# midi2board.net
KiCad netlist of a schematic drawn in EAGLE
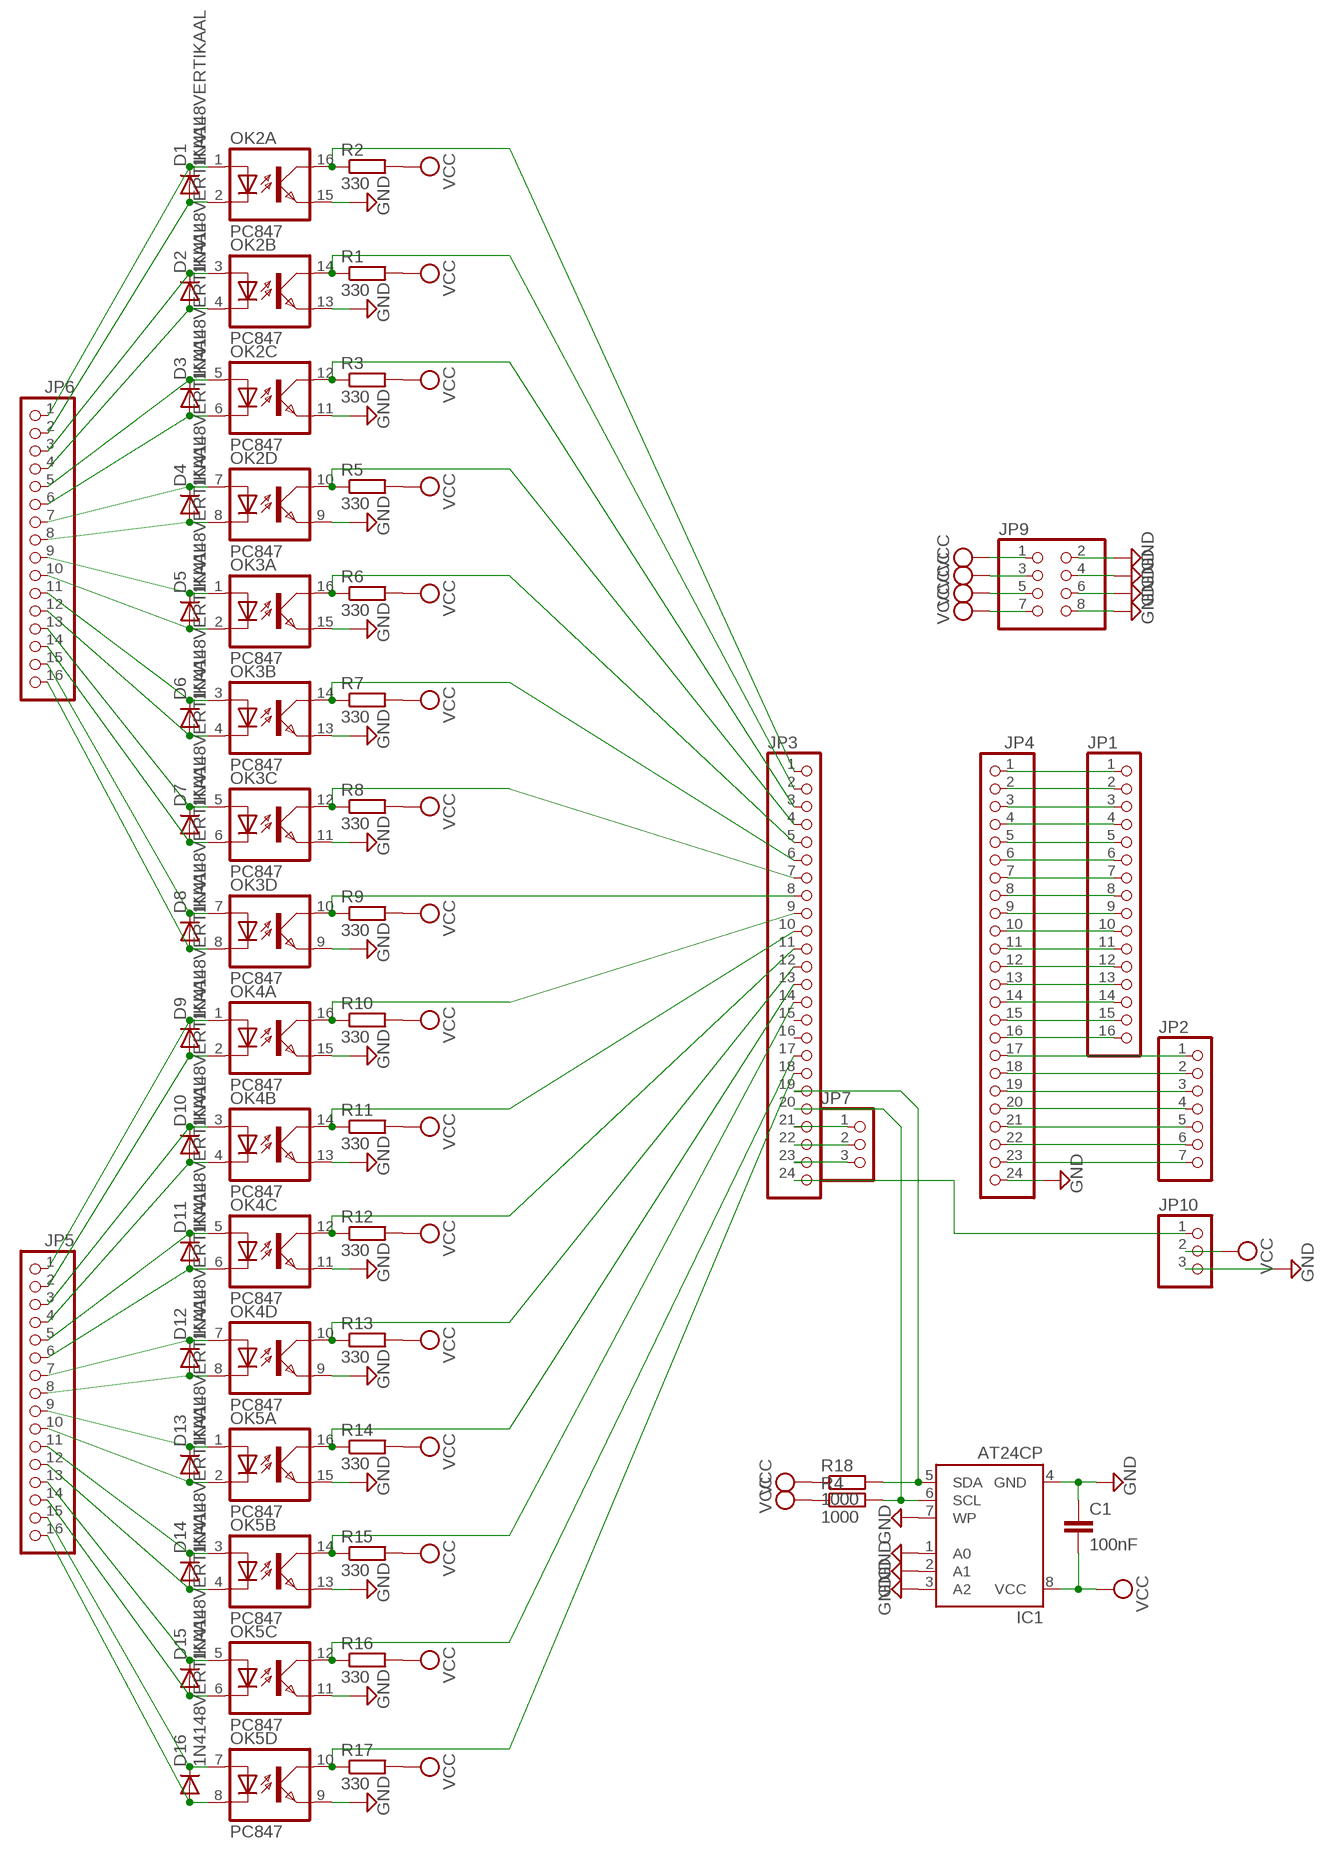
[diagram p0: schematic, sheet 1]

(export (version "E")
  (design (tool "Eeschema 10.0.6"))
  (components
    (comp (ref "C1")
      (value "100nF")
      (footprint "eagle-import:C5B2.5")
      (libsource (lib "eagle-import") (part "C5/2.5"))
    )
    (comp (ref "D1")
      (value "1N4148VERTIKAAL")
      (footprint "eagle-import:RAD2,5")
      (libsource (lib "eagle-import") (part "1N4148VERTIKAAL"))
    )
    (comp (ref "D2")
      (value "1N4148VERTIKAAL")
      (footprint "eagle-import:RAD2,5")
      (libsource (lib "eagle-import") (part "1N4148VERTIKAAL"))
    )
    (comp (ref "D3")
      (value "1N4148VERTIKAAL")
      (footprint "eagle-import:RAD2,5")
      (libsource (lib "eagle-import") (part "1N4148VERTIKAAL"))
    )
    (comp (ref "D4")
      (value "1N4148VERTIKAAL")
      (footprint "eagle-import:RAD2,5")
      (libsource (lib "eagle-import") (part "1N4148VERTIKAAL"))
    )
    (comp (ref "D5")
      (value "1N4148VERTIKAAL")
      (footprint "eagle-import:RAD2,5")
      (libsource (lib "eagle-import") (part "1N4148VERTIKAAL"))
    )
    (comp (ref "D6")
      (value "1N4148VERTIKAAL")
      (footprint "eagle-import:RAD2,5")
      (libsource (lib "eagle-import") (part "1N4148VERTIKAAL"))
    )
    (comp (ref "D7")
      (value "1N4148VERTIKAAL")
      (footprint "eagle-import:RAD2,5")
      (libsource (lib "eagle-import") (part "1N4148VERTIKAAL"))
    )
    (comp (ref "D8")
      (value "1N4148VERTIKAAL")
      (footprint "eagle-import:RAD2,5")
      (libsource (lib "eagle-import") (part "1N4148VERTIKAAL"))
    )
    (comp (ref "D9")
      (value "1N4148VERTIKAAL")
      (footprint "eagle-import:RAD2,5")
      (libsource (lib "eagle-import") (part "1N4148VERTIKAAL"))
    )
    (comp (ref "D10")
      (value "1N4148VERTIKAAL")
      (footprint "eagle-import:RAD2,5")
      (libsource (lib "eagle-import") (part "1N4148VERTIKAAL"))
    )
    (comp (ref "D11")
      (value "1N4148VERTIKAAL")
      (footprint "eagle-import:RAD2,5")
      (libsource (lib "eagle-import") (part "1N4148VERTIKAAL"))
    )
    (comp (ref "D12")
      (value "1N4148VERTIKAAL")
      (footprint "eagle-import:RAD2,5")
      (libsource (lib "eagle-import") (part "1N4148VERTIKAAL"))
    )
    (comp (ref "D13")
      (value "1N4148VERTIKAAL")
      (footprint "eagle-import:RAD2,5")
      (libsource (lib "eagle-import") (part "1N4148VERTIKAAL"))
    )
    (comp (ref "D14")
      (value "1N4148VERTIKAAL")
      (footprint "eagle-import:RAD2,5")
      (libsource (lib "eagle-import") (part "1N4148VERTIKAAL"))
    )
    (comp (ref "D15")
      (value "1N4148VERTIKAAL")
      (footprint "eagle-import:RAD2,5")
      (libsource (lib "eagle-import") (part "1N4148VERTIKAAL"))
    )
    (comp (ref "D16")
      (value "1N4148VERTIKAAL")
      (footprint "eagle-import:RAD2,5")
      (libsource (lib "eagle-import") (part "1N4148VERTIKAAL"))
    )
    (comp (ref "IC1")
      (value "AT24CP")
      (footprint "eagle-import:DIL08")
      (fields (field (name "MPN") "AT24C1024BW-SH-B"))
      (libsource (lib "eagle-import") (part "AT24CP"))
    )
    (comp (ref "JP1")
      (value "PINHD-1X16")
      (footprint "eagle-import:1X16")
      (libsource (lib "eagle-import") (part "PINHD-1X16"))
    )
    (comp (ref "JP2")
      (value "PINHD-1X7")
      (footprint "eagle-import:1X07")
      (libsource (lib "eagle-import") (part "PINHD-1X7"))
    )
    (comp (ref "JP3")
      (value "PINHD-1X24")
      (footprint "eagle-import:1X24")
      (libsource (lib "eagle-import") (part "PINHD-1X24"))
    )
    (comp (ref "JP4")
      (value "PINHD-1X24")
      (footprint "eagle-import:1X24")
      (libsource (lib "eagle-import") (part "PINHD-1X24"))
    )
    (comp (ref "JP5")
      (value "PINHD-1X16")
      (footprint "eagle-import:1X16")
      (libsource (lib "eagle-import") (part "PINHD-1X16"))
    )
    (comp (ref "JP6")
      (value "PINHD-1X16")
      (footprint "eagle-import:1X16")
      (libsource (lib "eagle-import") (part "PINHD-1X16"))
    )
    (comp (ref "JP7")
      (value "PINHD-1X3")
      (footprint "eagle-import:1X03")
      (libsource (lib "eagle-import") (part "PINHD-1X3"))
    )
    (comp (ref "JP9")
      (value "PINHD-2X4")
      (footprint "eagle-import:2X04")
      (libsource (lib "eagle-import") (part "PINHD-2X4"))
    )
    (comp (ref "JP10")
      (value "PINHD-1X3")
      (footprint "eagle-import:1X03")
      (libsource (lib "eagle-import") (part "PINHD-1X3"))
    )
    (comp (ref "OK2")
      (value "PC847")
      (footprint "eagle-import:DIL16")
      (libsource (lib "eagle-import") (part "PC847"))
    )
    (comp (ref "OK3")
      (value "PC847")
      (footprint "eagle-import:DIL16")
      (libsource (lib "eagle-import") (part "PC847"))
    )
    (comp (ref "OK4")
      (value "PC847")
      (footprint "eagle-import:DIL16")
      (libsource (lib "eagle-import") (part "PC847"))
    )
    (comp (ref "OK5")
      (value "PC847")
      (footprint "eagle-import:DIL16")
      (libsource (lib "eagle-import") (part "PC847"))
    )
    (comp (ref "R1")
      (value "330")
      (footprint "eagle-import:0207_10")
      (libsource (lib "eagle-import") (part "R-EU_0207/10"))
    )
    (comp (ref "R2")
      (value "330")
      (footprint "eagle-import:0207_10")
      (libsource (lib "eagle-import") (part "R-EU_0207/10"))
    )
    (comp (ref "R3")
      (value "330")
      (footprint "eagle-import:0207_10")
      (libsource (lib "eagle-import") (part "R-EU_0207/10"))
    )
    (comp (ref "R4")
      (value "1000")
      (footprint "eagle-import:0207_10")
      (libsource (lib "eagle-import") (part "R-EU_0207/10"))
    )
    (comp (ref "R5")
      (value "330")
      (footprint "eagle-import:0207_10")
      (libsource (lib "eagle-import") (part "R-EU_0207/10"))
    )
    (comp (ref "R6")
      (value "330")
      (footprint "eagle-import:0207_10")
      (libsource (lib "eagle-import") (part "R-EU_0207/10"))
    )
    (comp (ref "R7")
      (value "330")
      (footprint "eagle-import:0207_10")
      (libsource (lib "eagle-import") (part "R-EU_0207/10"))
    )
    (comp (ref "R8")
      (value "330")
      (footprint "eagle-import:0207_10")
      (libsource (lib "eagle-import") (part "R-EU_0207/10"))
    )
    (comp (ref "R9")
      (value "330")
      (footprint "eagle-import:0207_10")
      (libsource (lib "eagle-import") (part "R-EU_0207/10"))
    )
    (comp (ref "R10")
      (value "330")
      (footprint "eagle-import:0207_10")
      (libsource (lib "eagle-import") (part "R-EU_0207/10"))
    )
    (comp (ref "R11")
      (value "330")
      (footprint "eagle-import:0207_10")
      (libsource (lib "eagle-import") (part "R-EU_0207/10"))
    )
    (comp (ref "R12")
      (value "330")
      (footprint "eagle-import:0207_10")
      (libsource (lib "eagle-import") (part "R-EU_0207/10"))
    )
    (comp (ref "R13")
      (value "330")
      (footprint "eagle-import:0207_10")
      (libsource (lib "eagle-import") (part "R-EU_0207/10"))
    )
    (comp (ref "R14")
      (value "330")
      (footprint "eagle-import:0207_10")
      (libsource (lib "eagle-import") (part "R-EU_0207/10"))
    )
    (comp (ref "R15")
      (value "330")
      (footprint "eagle-import:0207_10")
      (libsource (lib "eagle-import") (part "R-EU_0207/10"))
    )
    (comp (ref "R16")
      (value "330")
      (footprint "eagle-import:0207_10")
      (libsource (lib "eagle-import") (part "R-EU_0207/10"))
    )
    (comp (ref "R17")
      (value "330")
      (footprint "eagle-import:0207_10")
      (libsource (lib "eagle-import") (part "R-EU_0207/10"))
    )
    (comp (ref "R18")
      (value "1000")
      (footprint "eagle-import:0207_10")
      (libsource (lib "eagle-import") (part "R-EU_0207/10"))
    )
  )
  (nets
    (net (code "1") (name "GND") (class "Default")
      (node (ref "C1") (pin "1") (pinfunction "1_1") (pintype "passive"))
      (node (ref "IC1") (pin "1") (pinfunction "A0_1") (pintype "input"))
      (node (ref "IC1") (pin "2") (pinfunction "A1_2") (pintype "input"))
      (node (ref "IC1") (pin "3") (pinfunction "A2_3") (pintype "input"))
      (node (ref "IC1") (pin "4") (pinfunction "GND_4") (pintype "power_in"))
      (node (ref "IC1") (pin "7") (pinfunction "WP_7") (pintype "input"))
      (node (ref "JP10") (pin "3") (pinfunction "3_3") (pintype "passive"))
      (node (ref "JP4") (pin "24") (pinfunction "24_24") (pintype "passive"))
      (node (ref "JP9") (pin "2") (pinfunction "2_2") (pintype "passive"))
      (node (ref "JP9") (pin "4") (pinfunction "4_4") (pintype "passive"))
      (node (ref "JP9") (pin "6") (pinfunction "6_6") (pintype "passive"))
      (node (ref "JP9") (pin "8") (pinfunction "8_8") (pintype "passive"))
      (node (ref "OK2") (pin "11") (pinfunction "EMIT_11") (pintype "passive"))
      (node (ref "OK2") (pin "13") (pinfunction "EMIT_13") (pintype "passive"))
      (node (ref "OK2") (pin "15") (pinfunction "EMIT_15") (pintype "passive"))
      (node (ref "OK2") (pin "9") (pinfunction "EMIT_9") (pintype "passive"))
      (node (ref "OK3") (pin "11") (pinfunction "EMIT_11") (pintype "passive"))
      (node (ref "OK3") (pin "13") (pinfunction "EMIT_13") (pintype "passive"))
      (node (ref "OK3") (pin "15") (pinfunction "EMIT_15") (pintype "passive"))
      (node (ref "OK3") (pin "9") (pinfunction "EMIT_9") (pintype "passive"))
      (node (ref "OK4") (pin "11") (pinfunction "EMIT_11") (pintype "passive"))
      (node (ref "OK4") (pin "13") (pinfunction "EMIT_13") (pintype "passive"))
      (node (ref "OK4") (pin "15") (pinfunction "EMIT_15") (pintype "passive"))
      (node (ref "OK4") (pin "9") (pinfunction "EMIT_9") (pintype "passive"))
      (node (ref "OK5") (pin "11") (pinfunction "EMIT_11") (pintype "passive"))
      (node (ref "OK5") (pin "13") (pinfunction "EMIT_13") (pintype "passive"))
      (node (ref "OK5") (pin "15") (pinfunction "EMIT_15") (pintype "passive"))
      (node (ref "OK5") (pin "9") (pinfunction "EMIT_9") (pintype "passive"))
    )
    (net (code "2") (name "Net-(IC1-SCL)") (class "Default")
      (node (ref "IC1") (pin "6") (pinfunction "SCL_6") (pintype "bidirectional"))
      (node (ref "JP3") (pin "20") (pinfunction "20_20") (pintype "passive"))
      (node (ref "R4") (pin "2") (pinfunction "2_2") (pintype "passive"))
    )
    (net (code "3") (name "Net-(IC1-SDA)") (class "Default")
      (node (ref "IC1") (pin "5") (pinfunction "SDA_5") (pintype "bidirectional"))
      (node (ref "JP3") (pin "19") (pinfunction "19_19") (pintype "passive"))
      (node (ref "R18") (pin "2") (pinfunction "2_2") (pintype "passive"))
    )
    (net (code "4") (name "Net-(JP1-Pad1)") (class "Default")
      (node (ref "JP1") (pin "1") (pinfunction "1_1") (pintype "passive"))
      (node (ref "JP4") (pin "1") (pinfunction "1_1") (pintype "passive"))
    )
    (net (code "5") (name "Net-(JP1-Pad2)") (class "Default")
      (node (ref "JP1") (pin "2") (pinfunction "2_2") (pintype "passive"))
      (node (ref "JP4") (pin "2") (pinfunction "2_2") (pintype "passive"))
    )
    (net (code "6") (name "Net-(JP1-Pad3)") (class "Default")
      (node (ref "JP1") (pin "3") (pinfunction "3_3") (pintype "passive"))
      (node (ref "JP4") (pin "3") (pinfunction "3_3") (pintype "passive"))
    )
    (net (code "7") (name "Net-(JP1-Pad4)") (class "Default")
      (node (ref "JP1") (pin "4") (pinfunction "4_4") (pintype "passive"))
      (node (ref "JP4") (pin "4") (pinfunction "4_4") (pintype "passive"))
    )
    (net (code "8") (name "Net-(JP1-Pad5)") (class "Default")
      (node (ref "JP1") (pin "5") (pinfunction "5_5") (pintype "passive"))
      (node (ref "JP4") (pin "5") (pinfunction "5_5") (pintype "passive"))
    )
    (net (code "9") (name "Net-(JP1-Pad6)") (class "Default")
      (node (ref "JP1") (pin "6") (pinfunction "6_6") (pintype "passive"))
      (node (ref "JP4") (pin "6") (pinfunction "6_6") (pintype "passive"))
    )
    (net (code "10") (name "Net-(JP1-Pad7)") (class "Default")
      (node (ref "JP1") (pin "7") (pinfunction "7_7") (pintype "passive"))
      (node (ref "JP4") (pin "7") (pinfunction "7_7") (pintype "passive"))
    )
    (net (code "11") (name "Net-(JP1-Pad8)") (class "Default")
      (node (ref "JP1") (pin "8") (pinfunction "8_8") (pintype "passive"))
      (node (ref "JP4") (pin "8") (pinfunction "8_8") (pintype "passive"))
    )
    (net (code "12") (name "Net-(JP1-Pad9)") (class "Default")
      (node (ref "JP1") (pin "9") (pinfunction "9_9") (pintype "passive"))
      (node (ref "JP4") (pin "9") (pinfunction "9_9") (pintype "passive"))
    )
    (net (code "13") (name "Net-(JP1-Pad10)") (class "Default")
      (node (ref "JP1") (pin "10") (pinfunction "10_10") (pintype "passive"))
      (node (ref "JP4") (pin "10") (pinfunction "10_10") (pintype "passive"))
    )
    (net (code "14") (name "Net-(JP1-Pad11)") (class "Default")
      (node (ref "JP1") (pin "11") (pinfunction "11_11") (pintype "passive"))
      (node (ref "JP4") (pin "11") (pinfunction "11_11") (pintype "passive"))
    )
    (net (code "15") (name "Net-(JP1-Pad12)") (class "Default")
      (node (ref "JP1") (pin "12") (pinfunction "12_12") (pintype "passive"))
      (node (ref "JP4") (pin "12") (pinfunction "12_12") (pintype "passive"))
    )
    (net (code "16") (name "Net-(JP1-Pad13)") (class "Default")
      (node (ref "JP1") (pin "13") (pinfunction "13_13") (pintype "passive"))
      (node (ref "JP4") (pin "13") (pinfunction "13_13") (pintype "passive"))
    )
    (net (code "17") (name "Net-(JP1-Pad14)") (class "Default")
      (node (ref "JP1") (pin "14") (pinfunction "14_14") (pintype "passive"))
      (node (ref "JP4") (pin "14") (pinfunction "14_14") (pintype "passive"))
    )
    (net (code "18") (name "Net-(JP1-Pad15)") (class "Default")
      (node (ref "JP1") (pin "15") (pinfunction "15_15") (pintype "passive"))
      (node (ref "JP4") (pin "15") (pinfunction "15_15") (pintype "passive"))
    )
    (net (code "19") (name "Net-(JP1-Pad16)") (class "Default")
      (node (ref "JP1") (pin "16") (pinfunction "16_16") (pintype "passive"))
      (node (ref "JP4") (pin "16") (pinfunction "16_16") (pintype "passive"))
    )
    (net (code "20") (name "Net-(JP2-Pad1)") (class "Default")
      (node (ref "JP2") (pin "1") (pinfunction "1_1") (pintype "passive"))
      (node (ref "JP4") (pin "17") (pinfunction "17_17") (pintype "passive"))
    )
    (net (code "21") (name "Net-(JP2-Pad2)") (class "Default")
      (node (ref "JP2") (pin "2") (pinfunction "2_2") (pintype "passive"))
      (node (ref "JP4") (pin "18") (pinfunction "18_18") (pintype "passive"))
    )
    (net (code "22") (name "Net-(JP2-Pad3)") (class "Default")
      (node (ref "JP2") (pin "3") (pinfunction "3_3") (pintype "passive"))
      (node (ref "JP4") (pin "19") (pinfunction "19_19") (pintype "passive"))
    )
    (net (code "23") (name "Net-(JP2-Pad4)") (class "Default")
      (node (ref "JP2") (pin "4") (pinfunction "4_4") (pintype "passive"))
      (node (ref "JP4") (pin "20") (pinfunction "20_20") (pintype "passive"))
    )
    (net (code "24") (name "Net-(JP2-Pad5)") (class "Default")
      (node (ref "JP2") (pin "5") (pinfunction "5_5") (pintype "passive"))
      (node (ref "JP4") (pin "21") (pinfunction "21_21") (pintype "passive"))
    )
    (net (code "25") (name "Net-(JP2-Pad6)") (class "Default")
      (node (ref "JP2") (pin "6") (pinfunction "6_6") (pintype "passive"))
      (node (ref "JP4") (pin "22") (pinfunction "22_22") (pintype "passive"))
    )
    (net (code "26") (name "Net-(JP2-Pad7)") (class "Default")
      (node (ref "JP2") (pin "7") (pinfunction "7_7") (pintype "passive"))
      (node (ref "JP4") (pin "23") (pinfunction "23_23") (pintype "passive"))
    )
    (net (code "27") (name "Net-(JP3-Pad21)") (class "Default")
      (node (ref "JP3") (pin "21") (pinfunction "21_21") (pintype "passive"))
      (node (ref "JP7") (pin "1") (pinfunction "1_1") (pintype "passive"))
    )
    (net (code "28") (name "Net-(JP3-Pad22)") (class "Default")
      (node (ref "JP3") (pin "22") (pinfunction "22_22") (pintype "passive"))
      (node (ref "JP7") (pin "2") (pinfunction "2_2") (pintype "passive"))
    )
    (net (code "29") (name "Net-(JP3-Pad23)") (class "Default")
      (node (ref "JP3") (pin "23") (pinfunction "23_23") (pintype "passive"))
      (node (ref "JP7") (pin "3") (pinfunction "3_3") (pintype "passive"))
    )
    (net (code "30") (name "Net-(JP10-Pad1)") (class "Default")
      (node (ref "JP10") (pin "1") (pinfunction "1_1") (pintype "passive"))
      (node (ref "JP3") (pin "24") (pinfunction "24_24") (pintype "passive"))
    )
    (net (code "31") (name "Net-(OK2A-A)") (class "Default")
      (node (ref "D1") (pin "C") (pinfunction "C_C") (pintype "passive"))
      (node (ref "JP6") (pin "1") (pinfunction "1_1") (pintype "passive"))
      (node (ref "OK2") (pin "1") (pinfunction "A_1") (pintype "passive"))
    )
    (net (code "32") (name "Net-(OK2A-C)") (class "Default")
      (node (ref "D1") (pin "A") (pinfunction "A_A") (pintype "passive"))
      (node (ref "JP6") (pin "2") (pinfunction "2_2") (pintype "passive"))
      (node (ref "OK2") (pin "2") (pinfunction "C_2") (pintype "passive"))
    )
    (net (code "33") (name "Net-(OK2A-COL)") (class "Default")
      (node (ref "JP3") (pin "1") (pinfunction "1_1") (pintype "passive"))
      (node (ref "OK2") (pin "16") (pinfunction "COL_16") (pintype "passive"))
      (node (ref "R2") (pin "1") (pinfunction "1_1") (pintype "passive"))
    )
    (net (code "34") (name "Net-(OK2B-A)") (class "Default")
      (node (ref "D2") (pin "C") (pinfunction "C_C") (pintype "passive"))
      (node (ref "JP6") (pin "3") (pinfunction "3_3") (pintype "passive"))
      (node (ref "OK2") (pin "3") (pinfunction "A_3") (pintype "passive"))
    )
    (net (code "35") (name "Net-(OK2B-C)") (class "Default")
      (node (ref "D2") (pin "A") (pinfunction "A_A") (pintype "passive"))
      (node (ref "JP6") (pin "4") (pinfunction "4_4") (pintype "passive"))
      (node (ref "OK2") (pin "4") (pinfunction "C_4") (pintype "passive"))
    )
    (net (code "36") (name "Net-(OK2B-COL)") (class "Default")
      (node (ref "JP3") (pin "2") (pinfunction "2_2") (pintype "passive"))
      (node (ref "OK2") (pin "14") (pinfunction "COL_14") (pintype "passive"))
      (node (ref "R1") (pin "1") (pinfunction "1_1") (pintype "passive"))
    )
    (net (code "37") (name "Net-(OK2C-A)") (class "Default")
      (node (ref "D3") (pin "C") (pinfunction "C_C") (pintype "passive"))
      (node (ref "JP6") (pin "5") (pinfunction "5_5") (pintype "passive"))
      (node (ref "OK2") (pin "5") (pinfunction "A_5") (pintype "passive"))
    )
    (net (code "38") (name "Net-(OK2C-C)") (class "Default")
      (node (ref "D3") (pin "A") (pinfunction "A_A") (pintype "passive"))
      (node (ref "JP6") (pin "6") (pinfunction "6_6") (pintype "passive"))
      (node (ref "OK2") (pin "6") (pinfunction "C_6") (pintype "passive"))
    )
    (net (code "39") (name "Net-(OK2C-COL)") (class "Default")
      (node (ref "JP3") (pin "3") (pinfunction "3_3") (pintype "passive"))
      (node (ref "OK2") (pin "12") (pinfunction "COL_12") (pintype "passive"))
      (node (ref "R3") (pin "1") (pinfunction "1_1") (pintype "passive"))
    )
    (net (code "40") (name "Net-(OK2D-A)") (class "Default")
      (node (ref "D4") (pin "C") (pinfunction "C_C") (pintype "passive"))
      (node (ref "JP6") (pin "7") (pinfunction "7_7") (pintype "passive"))
      (node (ref "OK2") (pin "7") (pinfunction "A_7") (pintype "passive"))
    )
    (net (code "41") (name "Net-(OK2D-C)") (class "Default")
      (node (ref "D4") (pin "A") (pinfunction "A_A") (pintype "passive"))
      (node (ref "JP6") (pin "8") (pinfunction "8_8") (pintype "passive"))
      (node (ref "OK2") (pin "8") (pinfunction "C_8") (pintype "passive"))
    )
    (net (code "42") (name "Net-(OK2D-COL)") (class "Default")
      (node (ref "JP3") (pin "4") (pinfunction "4_4") (pintype "passive"))
      (node (ref "OK2") (pin "10") (pinfunction "COL_10") (pintype "passive"))
      (node (ref "R5") (pin "1") (pinfunction "1_1") (pintype "passive"))
    )
    (net (code "43") (name "Net-(OK3A-A)") (class "Default")
      (node (ref "D5") (pin "C") (pinfunction "C_C") (pintype "passive"))
      (node (ref "JP6") (pin "9") (pinfunction "9_9") (pintype "passive"))
      (node (ref "OK3") (pin "1") (pinfunction "A_1") (pintype "passive"))
    )
    (net (code "44") (name "Net-(OK3A-C)") (class "Default")
      (node (ref "D5") (pin "A") (pinfunction "A_A") (pintype "passive"))
      (node (ref "JP6") (pin "10") (pinfunction "10_10") (pintype "passive"))
      (node (ref "OK3") (pin "2") (pinfunction "C_2") (pintype "passive"))
    )
    (net (code "45") (name "Net-(OK3A-COL)") (class "Default")
      (node (ref "JP3") (pin "5") (pinfunction "5_5") (pintype "passive"))
      (node (ref "OK3") (pin "16") (pinfunction "COL_16") (pintype "passive"))
      (node (ref "R6") (pin "1") (pinfunction "1_1") (pintype "passive"))
    )
    (net (code "46") (name "Net-(OK3B-A)") (class "Default")
      (node (ref "D6") (pin "C") (pinfunction "C_C") (pintype "passive"))
      (node (ref "JP6") (pin "11") (pinfunction "11_11") (pintype "passive"))
      (node (ref "OK3") (pin "3") (pinfunction "A_3") (pintype "passive"))
    )
    (net (code "47") (name "Net-(OK3B-C)") (class "Default")
      (node (ref "D6") (pin "A") (pinfunction "A_A") (pintype "passive"))
      (node (ref "JP6") (pin "12") (pinfunction "12_12") (pintype "passive"))
      (node (ref "OK3") (pin "4") (pinfunction "C_4") (pintype "passive"))
    )
    (net (code "48") (name "Net-(OK3B-COL)") (class "Default")
      (node (ref "JP3") (pin "6") (pinfunction "6_6") (pintype "passive"))
      (node (ref "OK3") (pin "14") (pinfunction "COL_14") (pintype "passive"))
      (node (ref "R7") (pin "1") (pinfunction "1_1") (pintype "passive"))
    )
    (net (code "49") (name "Net-(OK3C-A)") (class "Default")
      (node (ref "D7") (pin "C") (pinfunction "C_C") (pintype "passive"))
      (node (ref "JP6") (pin "13") (pinfunction "13_13") (pintype "passive"))
      (node (ref "OK3") (pin "5") (pinfunction "A_5") (pintype "passive"))
    )
    (net (code "50") (name "Net-(OK3C-C)") (class "Default")
      (node (ref "D7") (pin "A") (pinfunction "A_A") (pintype "passive"))
      (node (ref "JP6") (pin "14") (pinfunction "14_14") (pintype "passive"))
      (node (ref "OK3") (pin "6") (pinfunction "C_6") (pintype "passive"))
    )
    (net (code "51") (name "Net-(OK3C-COL)") (class "Default")
      (node (ref "JP3") (pin "7") (pinfunction "7_7") (pintype "passive"))
      (node (ref "OK3") (pin "12") (pinfunction "COL_12") (pintype "passive"))
      (node (ref "R8") (pin "1") (pinfunction "1_1") (pintype "passive"))
    )
    (net (code "52") (name "Net-(OK3D-A)") (class "Default")
      (node (ref "D8") (pin "C") (pinfunction "C_C") (pintype "passive"))
      (node (ref "JP6") (pin "15") (pinfunction "15_15") (pintype "passive"))
      (node (ref "OK3") (pin "7") (pinfunction "A_7") (pintype "passive"))
    )
    (net (code "53") (name "Net-(OK3D-C)") (class "Default")
      (node (ref "D8") (pin "A") (pinfunction "A_A") (pintype "passive"))
      (node (ref "JP6") (pin "16") (pinfunction "16_16") (pintype "passive"))
      (node (ref "OK3") (pin "8") (pinfunction "C_8") (pintype "passive"))
    )
    (net (code "54") (name "Net-(OK3D-COL)") (class "Default")
      (node (ref "JP3") (pin "8") (pinfunction "8_8") (pintype "passive"))
      (node (ref "OK3") (pin "10") (pinfunction "COL_10") (pintype "passive"))
      (node (ref "R9") (pin "1") (pinfunction "1_1") (pintype "passive"))
    )
    (net (code "55") (name "Net-(OK4A-A)") (class "Default")
      (node (ref "D9") (pin "C") (pinfunction "C_C") (pintype "passive"))
      (node (ref "JP5") (pin "1") (pinfunction "1_1") (pintype "passive"))
      (node (ref "OK4") (pin "1") (pinfunction "A_1") (pintype "passive"))
    )
    (net (code "56") (name "Net-(OK4A-C)") (class "Default")
      (node (ref "D9") (pin "A") (pinfunction "A_A") (pintype "passive"))
      (node (ref "JP5") (pin "2") (pinfunction "2_2") (pintype "passive"))
      (node (ref "OK4") (pin "2") (pinfunction "C_2") (pintype "passive"))
    )
    (net (code "57") (name "Net-(OK4A-COL)") (class "Default")
      (node (ref "JP3") (pin "9") (pinfunction "9_9") (pintype "passive"))
      (node (ref "OK4") (pin "16") (pinfunction "COL_16") (pintype "passive"))
      (node (ref "R10") (pin "1") (pinfunction "1_1") (pintype "passive"))
    )
    (net (code "58") (name "Net-(OK4B-A)") (class "Default")
      (node (ref "D10") (pin "C") (pinfunction "C_C") (pintype "passive"))
      (node (ref "JP5") (pin "3") (pinfunction "3_3") (pintype "passive"))
      (node (ref "OK4") (pin "3") (pinfunction "A_3") (pintype "passive"))
    )
    (net (code "59") (name "Net-(OK4B-C)") (class "Default")
      (node (ref "D10") (pin "A") (pinfunction "A_A") (pintype "passive"))
      (node (ref "JP5") (pin "4") (pinfunction "4_4") (pintype "passive"))
      (node (ref "OK4") (pin "4") (pinfunction "C_4") (pintype "passive"))
    )
    (net (code "60") (name "Net-(OK4B-COL)") (class "Default")
      (node (ref "JP3") (pin "10") (pinfunction "10_10") (pintype "passive"))
      (node (ref "OK4") (pin "14") (pinfunction "COL_14") (pintype "passive"))
      (node (ref "R11") (pin "1") (pinfunction "1_1") (pintype "passive"))
    )
    (net (code "61") (name "Net-(OK4C-A)") (class "Default")
      (node (ref "D11") (pin "C") (pinfunction "C_C") (pintype "passive"))
      (node (ref "JP5") (pin "5") (pinfunction "5_5") (pintype "passive"))
      (node (ref "OK4") (pin "5") (pinfunction "A_5") (pintype "passive"))
    )
    (net (code "62") (name "Net-(OK4C-C)") (class "Default")
      (node (ref "D11") (pin "A") (pinfunction "A_A") (pintype "passive"))
      (node (ref "JP5") (pin "6") (pinfunction "6_6") (pintype "passive"))
      (node (ref "OK4") (pin "6") (pinfunction "C_6") (pintype "passive"))
    )
    (net (code "63") (name "Net-(OK4C-COL)") (class "Default")
      (node (ref "JP3") (pin "11") (pinfunction "11_11") (pintype "passive"))
      (node (ref "OK4") (pin "12") (pinfunction "COL_12") (pintype "passive"))
      (node (ref "R12") (pin "1") (pinfunction "1_1") (pintype "passive"))
    )
    (net (code "64") (name "Net-(OK4D-A)") (class "Default")
      (node (ref "D12") (pin "C") (pinfunction "C_C") (pintype "passive"))
      (node (ref "JP5") (pin "7") (pinfunction "7_7") (pintype "passive"))
      (node (ref "OK4") (pin "7") (pinfunction "A_7") (pintype "passive"))
    )
    (net (code "65") (name "Net-(OK4D-C)") (class "Default")
      (node (ref "D12") (pin "A") (pinfunction "A_A") (pintype "passive"))
      (node (ref "JP5") (pin "8") (pinfunction "8_8") (pintype "passive"))
      (node (ref "OK4") (pin "8") (pinfunction "C_8") (pintype "passive"))
    )
    (net (code "66") (name "Net-(OK4D-COL)") (class "Default")
      (node (ref "JP3") (pin "12") (pinfunction "12_12") (pintype "passive"))
      (node (ref "OK4") (pin "10") (pinfunction "COL_10") (pintype "passive"))
      (node (ref "R13") (pin "1") (pinfunction "1_1") (pintype "passive"))
    )
    (net (code "67") (name "Net-(OK5A-A)") (class "Default")
      (node (ref "D13") (pin "C") (pinfunction "C_C") (pintype "passive"))
      (node (ref "JP5") (pin "9") (pinfunction "9_9") (pintype "passive"))
      (node (ref "OK5") (pin "1") (pinfunction "A_1") (pintype "passive"))
    )
    (net (code "68") (name "Net-(OK5A-C)") (class "Default")
      (node (ref "D13") (pin "A") (pinfunction "A_A") (pintype "passive"))
      (node (ref "JP5") (pin "10") (pinfunction "10_10") (pintype "passive"))
      (node (ref "OK5") (pin "2") (pinfunction "C_2") (pintype "passive"))
    )
    (net (code "69") (name "Net-(OK5A-COL)") (class "Default")
      (node (ref "JP3") (pin "13") (pinfunction "13_13") (pintype "passive"))
      (node (ref "OK5") (pin "16") (pinfunction "COL_16") (pintype "passive"))
      (node (ref "R14") (pin "1") (pinfunction "1_1") (pintype "passive"))
    )
    (net (code "70") (name "Net-(OK5B-A)") (class "Default")
      (node (ref "D14") (pin "C") (pinfunction "C_C") (pintype "passive"))
      (node (ref "JP5") (pin "11") (pinfunction "11_11") (pintype "passive"))
      (node (ref "OK5") (pin "3") (pinfunction "A_3") (pintype "passive"))
    )
    (net (code "71") (name "Net-(OK5B-C)") (class "Default")
      (node (ref "D14") (pin "A") (pinfunction "A_A") (pintype "passive"))
      (node (ref "JP5") (pin "12") (pinfunction "12_12") (pintype "passive"))
      (node (ref "OK5") (pin "4") (pinfunction "C_4") (pintype "passive"))
    )
    (net (code "72") (name "Net-(OK5B-COL)") (class "Default")
      (node (ref "JP3") (pin "14") (pinfunction "14_14") (pintype "passive"))
      (node (ref "OK5") (pin "14") (pinfunction "COL_14") (pintype "passive"))
      (node (ref "R15") (pin "1") (pinfunction "1_1") (pintype "passive"))
    )
    (net (code "73") (name "Net-(OK5C-A)") (class "Default")
      (node (ref "D15") (pin "C") (pinfunction "C_C") (pintype "passive"))
      (node (ref "JP5") (pin "13") (pinfunction "13_13") (pintype "passive"))
      (node (ref "OK5") (pin "5") (pinfunction "A_5") (pintype "passive"))
    )
    (net (code "74") (name "Net-(OK5C-C)") (class "Default")
      (node (ref "D15") (pin "A") (pinfunction "A_A") (pintype "passive"))
      (node (ref "JP5") (pin "14") (pinfunction "14_14") (pintype "passive"))
      (node (ref "OK5") (pin "6") (pinfunction "C_6") (pintype "passive"))
    )
    (net (code "75") (name "Net-(OK5C-COL)") (class "Default")
      (node (ref "JP3") (pin "17") (pinfunction "17_17") (pintype "passive"))
      (node (ref "OK5") (pin "12") (pinfunction "COL_12") (pintype "passive"))
      (node (ref "R16") (pin "1") (pinfunction "1_1") (pintype "passive"))
    )
    (net (code "76") (name "Net-(OK5D-A)") (class "Default")
      (node (ref "D16") (pin "C") (pinfunction "C_C") (pintype "passive"))
      (node (ref "JP5") (pin "15") (pinfunction "15_15") (pintype "passive"))
      (node (ref "OK5") (pin "7") (pinfunction "A_7") (pintype "passive"))
    )
    (net (code "77") (name "Net-(OK5D-C)") (class "Default")
      (node (ref "D16") (pin "A") (pinfunction "A_A") (pintype "passive"))
      (node (ref "JP5") (pin "16") (pinfunction "16_16") (pintype "passive"))
      (node (ref "OK5") (pin "8") (pinfunction "C_8") (pintype "passive"))
    )
    (net (code "78") (name "Net-(OK5D-COL)") (class "Default")
      (node (ref "JP3") (pin "18") (pinfunction "18_18") (pintype "passive"))
      (node (ref "OK5") (pin "10") (pinfunction "COL_10") (pintype "passive"))
      (node (ref "R17") (pin "1") (pinfunction "1_1") (pintype "passive"))
    )
    (net (code "79") (name "VCC") (class "Default")
      (node (ref "C1") (pin "2") (pinfunction "2_2") (pintype "passive"))
      (node (ref "IC1") (pin "8") (pinfunction "VCC_8") (pintype "power_in"))
      (node (ref "JP10") (pin "2") (pinfunction "2_2") (pintype "passive"))
      (node (ref "JP9") (pin "1") (pinfunction "1_1") (pintype "passive"))
      (node (ref "JP9") (pin "3") (pinfunction "3_3") (pintype "passive"))
      (node (ref "JP9") (pin "5") (pinfunction "5_5") (pintype "passive"))
      (node (ref "JP9") (pin "7") (pinfunction "7_7") (pintype "passive"))
      (node (ref "R1") (pin "2") (pinfunction "2_2") (pintype "passive"))
      (node (ref "R10") (pin "2") (pinfunction "2_2") (pintype "passive"))
      (node (ref "R11") (pin "2") (pinfunction "2_2") (pintype "passive"))
      (node (ref "R12") (pin "2") (pinfunction "2_2") (pintype "passive"))
      (node (ref "R13") (pin "2") (pinfunction "2_2") (pintype "passive"))
      (node (ref "R14") (pin "2") (pinfunction "2_2") (pintype "passive"))
      (node (ref "R15") (pin "2") (pinfunction "2_2") (pintype "passive"))
      (node (ref "R16") (pin "2") (pinfunction "2_2") (pintype "passive"))
      (node (ref "R17") (pin "2") (pinfunction "2_2") (pintype "passive"))
      (node (ref "R18") (pin "1") (pinfunction "1_1") (pintype "passive"))
      (node (ref "R2") (pin "2") (pinfunction "2_2") (pintype "passive"))
      (node (ref "R3") (pin "2") (pinfunction "2_2") (pintype "passive"))
      (node (ref "R4") (pin "1") (pinfunction "1_1") (pintype "passive"))
      (node (ref "R5") (pin "2") (pinfunction "2_2") (pintype "passive"))
      (node (ref "R6") (pin "2") (pinfunction "2_2") (pintype "passive"))
      (node (ref "R7") (pin "2") (pinfunction "2_2") (pintype "passive"))
      (node (ref "R8") (pin "2") (pinfunction "2_2") (pintype "passive"))
      (node (ref "R9") (pin "2") (pinfunction "2_2") (pintype "passive"))
    )
    (net (code "80") (name "unconnected-(JP3-Pad15)") (class "Default")
      (node (ref "JP3") (pin "15") (pinfunction "15_15") (pintype "passive"))
    )
    (net (code "81") (name "unconnected-(JP3-Pad16)") (class "Default")
      (node (ref "JP3") (pin "16") (pinfunction "16_16") (pintype "passive"))
    )
  )
)
